# source_eagle.net
KiCad netlist of a schematic drawn in EAGLE
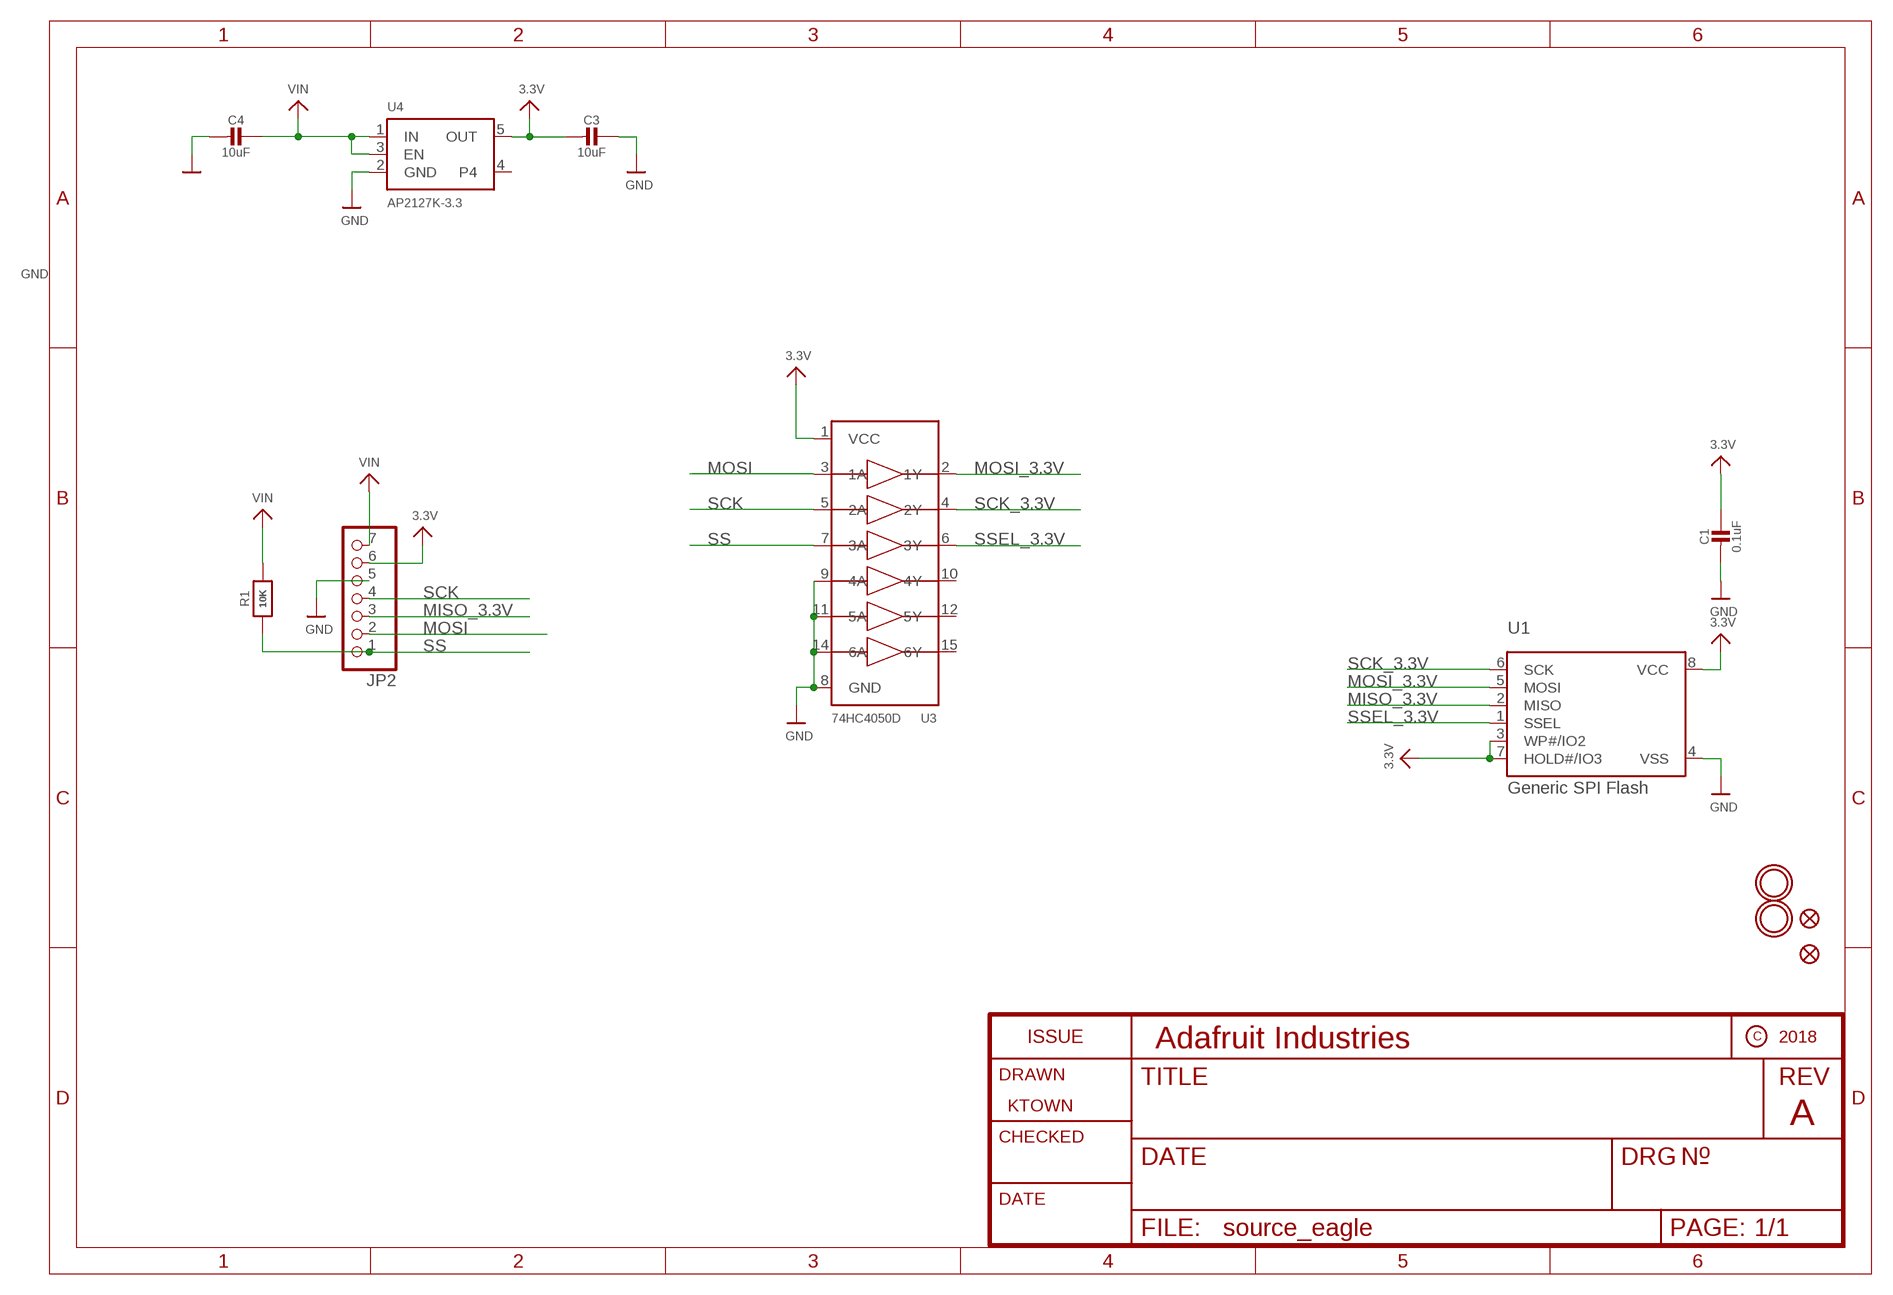
[diagram p0: schematic, sheet 1]

(export (version "E")
  (design (tool "Eeschema 10.0.6"))
  (components
    (comp (ref "C1")
      (value "0.1uF")
      (footprint "eagle-import:0603-NO")
      (libsource (lib "eagle-import") (part "CAP_CERAMIC0603_NO"))
    )
    (comp (ref "C3")
      (value "10uF")
      (footprint "eagle-import:0805-NO")
      (libsource (lib "eagle-import") (part "CAP_CERAMIC0805-NOOUTLINE"))
    )
    (comp (ref "C4")
      (value "10uF")
      (footprint "eagle-import:0805-NO")
      (libsource (lib "eagle-import") (part "CAP_CERAMIC0805-NOOUTLINE"))
    )
    (comp (ref "FID2")
      (value "FIDUCIAL_1MM")
      (footprint "eagle-import:FIDUCIAL_1MM")
      (libsource (lib "eagle-import") (part "FIDUCIAL_1MM"))
    )
    (comp (ref "FID3")
      (value "FIDUCIAL_1MM")
      (footprint "eagle-import:FIDUCIAL_1MM")
      (libsource (lib "eagle-import") (part "FIDUCIAL_1MM"))
    )
    (comp (ref "JP2")
      (value "HEADER-1X770MIL")
      (footprint "eagle-import:1X07_ROUND_70")
      (libsource (lib "eagle-import") (part "HEADER-1X770MIL"))
    )
    (comp (ref "R1")
      (value "10K")
      (footprint "eagle-import:0603-NO")
      (libsource (lib "eagle-import") (part "RESISTOR_0603_NOOUT"))
    )
    (comp (ref "U$16")
      (value "MOUNTINGHOLE2.5")
      (footprint "eagle-import:MOUNTINGHOLE_2.5_PLATED")
      (libsource (lib "eagle-import") (part "MOUNTINGHOLE2.5"))
    )
    (comp (ref "U$17")
      (value "MOUNTINGHOLE2.5")
      (footprint "eagle-import:MOUNTINGHOLE_2.5_PLATED")
      (libsource (lib "eagle-import") (part "MOUNTINGHOLE2.5"))
    )
    (comp (ref "U1")
      (value "Generic SPI Flash")
      (footprint "eagle-import:SOIC8_208MIL")
      (libsource (lib "eagle-import") (part "SPIFLASH_8PIN208MIL"))
    )
    (comp (ref "U3")
      (value "74HC4050D")
      (footprint "eagle-import:TSSOP16")
      (libsource (lib "eagle-import") (part "74HC4050DTSSOP"))
    )
    (comp (ref "U4")
      (value "AP2127K-3.3")
      (footprint "eagle-import:SOT23-5")
      (libsource (lib "eagle-import") (part "VREG_SOT23-5"))
    )
  )
  (nets
    (net (code "1") (name "/MISO_3.3V") (class "Default")
      (node (ref "JP2") (pin "3") (pinfunction "3_3") (pintype "passive"))
      (node (ref "U1") (pin "2") (pinfunction "MISO_2") (pintype "bidirectional"))
    )
    (net (code "2") (name "/MOSI") (class "Default")
      (node (ref "JP2") (pin "2") (pinfunction "2_2") (pintype "passive"))
      (node (ref "U3") (pin "3") (pinfunction "1A_3") (pintype "bidirectional"))
    )
    (net (code "3") (name "/MOSI_3.3V") (class "Default")
      (node (ref "U1") (pin "5") (pinfunction "MOSI_5") (pintype "bidirectional"))
      (node (ref "U3") (pin "2") (pinfunction "1Y_2") (pintype "bidirectional"))
    )
    (net (code "4") (name "/SCK") (class "Default")
      (node (ref "JP2") (pin "4") (pinfunction "4_4") (pintype "passive"))
      (node (ref "U3") (pin "5") (pinfunction "2A_5") (pintype "bidirectional"))
    )
    (net (code "5") (name "/SCK_3.3V") (class "Default")
      (node (ref "U1") (pin "6") (pinfunction "SCK_6") (pintype "bidirectional"))
      (node (ref "U3") (pin "4") (pinfunction "2Y_4") (pintype "bidirectional"))
    )
    (net (code "6") (name "/SS") (class "Default")
      (node (ref "JP2") (pin "1") (pinfunction "1_1") (pintype "passive"))
      (node (ref "R1") (pin "1") (pinfunction "1_1") (pintype "passive"))
      (node (ref "U3") (pin "7") (pinfunction "3A_7") (pintype "bidirectional"))
    )
    (net (code "7") (name "/SSEL_3.3V") (class "Default")
      (node (ref "U1") (pin "1") (pinfunction "SSEL_1") (pintype "bidirectional"))
      (node (ref "U3") (pin "6") (pinfunction "3Y_6") (pintype "bidirectional"))
    )
    (net (code "8") (name "3.3V") (class "Default")
      (node (ref "C1") (pin "1") (pinfunction "1_1") (pintype "passive"))
      (node (ref "C3") (pin "2") (pinfunction "2_2") (pintype "passive"))
      (node (ref "JP2") (pin "6") (pinfunction "6_6") (pintype "passive"))
      (node (ref "U1") (pin "3") (pinfunction "WP#/IO2_3") (pintype "bidirectional"))
      (node (ref "U1") (pin "7") (pinfunction "HOLD#/IO3_7") (pintype "bidirectional"))
      (node (ref "U1") (pin "8") (pinfunction "VCC_8") (pintype "bidirectional"))
      (node (ref "U3") (pin "1") (pinfunction "VCC_1") (pintype "bidirectional"))
      (node (ref "U4") (pin "5") (pinfunction "OUT_5") (pintype "power_in"))
    )
    (net (code "9") (name "GND") (class "Default")
      (node (ref "C1") (pin "2") (pinfunction "2_2") (pintype "passive"))
      (node (ref "C3") (pin "1") (pinfunction "1_1") (pintype "passive"))
      (node (ref "C4") (pin "2") (pinfunction "2_2") (pintype "passive"))
      (node (ref "JP2") (pin "5") (pinfunction "5_5") (pintype "passive"))
      (node (ref "U1") (pin "4") (pinfunction "VSS_4") (pintype "bidirectional"))
      (node (ref "U3") (pin "11") (pinfunction "5A_11") (pintype "bidirectional"))
      (node (ref "U3") (pin "14") (pinfunction "6A_14") (pintype "bidirectional"))
      (node (ref "U3") (pin "8") (pinfunction "GND_8") (pintype "bidirectional"))
      (node (ref "U3") (pin "9") (pinfunction "4A_9") (pintype "bidirectional"))
      (node (ref "U4") (pin "2") (pinfunction "GND_2") (pintype "power_in"))
    )
    (net (code "10") (name "VIN") (class "Default")
      (node (ref "C4") (pin "1") (pinfunction "1_1") (pintype "passive"))
      (node (ref "JP2") (pin "7") (pinfunction "7_7") (pintype "passive"))
      (node (ref "R1") (pin "2") (pinfunction "2_2") (pintype "passive"))
      (node (ref "U4") (pin "1") (pinfunction "IN_1") (pintype "power_in"))
      (node (ref "U4") (pin "3") (pinfunction "EN_3") (pintype "input"))
    )
    (net (code "11") (name "unconnected-(U3-4Y-Pad10)") (class "Default")
      (node (ref "U3") (pin "10") (pinfunction "4Y_10") (pintype "bidirectional"))
    )
    (net (code "12") (name "unconnected-(U3-5Y-Pad12)") (class "Default")
      (node (ref "U3") (pin "12") (pinfunction "5Y_12") (pintype "bidirectional"))
    )
    (net (code "13") (name "unconnected-(U3-6Y-Pad15)") (class "Default")
      (node (ref "U3") (pin "15") (pinfunction "6Y_15") (pintype "bidirectional"))
    )
    (net (code "14") (name "unconnected-(U4-P4-Pad4)") (class "Default")
      (node (ref "U4") (pin "4") (pinfunction "P4_4") (pintype "bidirectional"))
    )
  )
)
